# M993.net
KiCad netlist of a schematic drawn in EAGLE
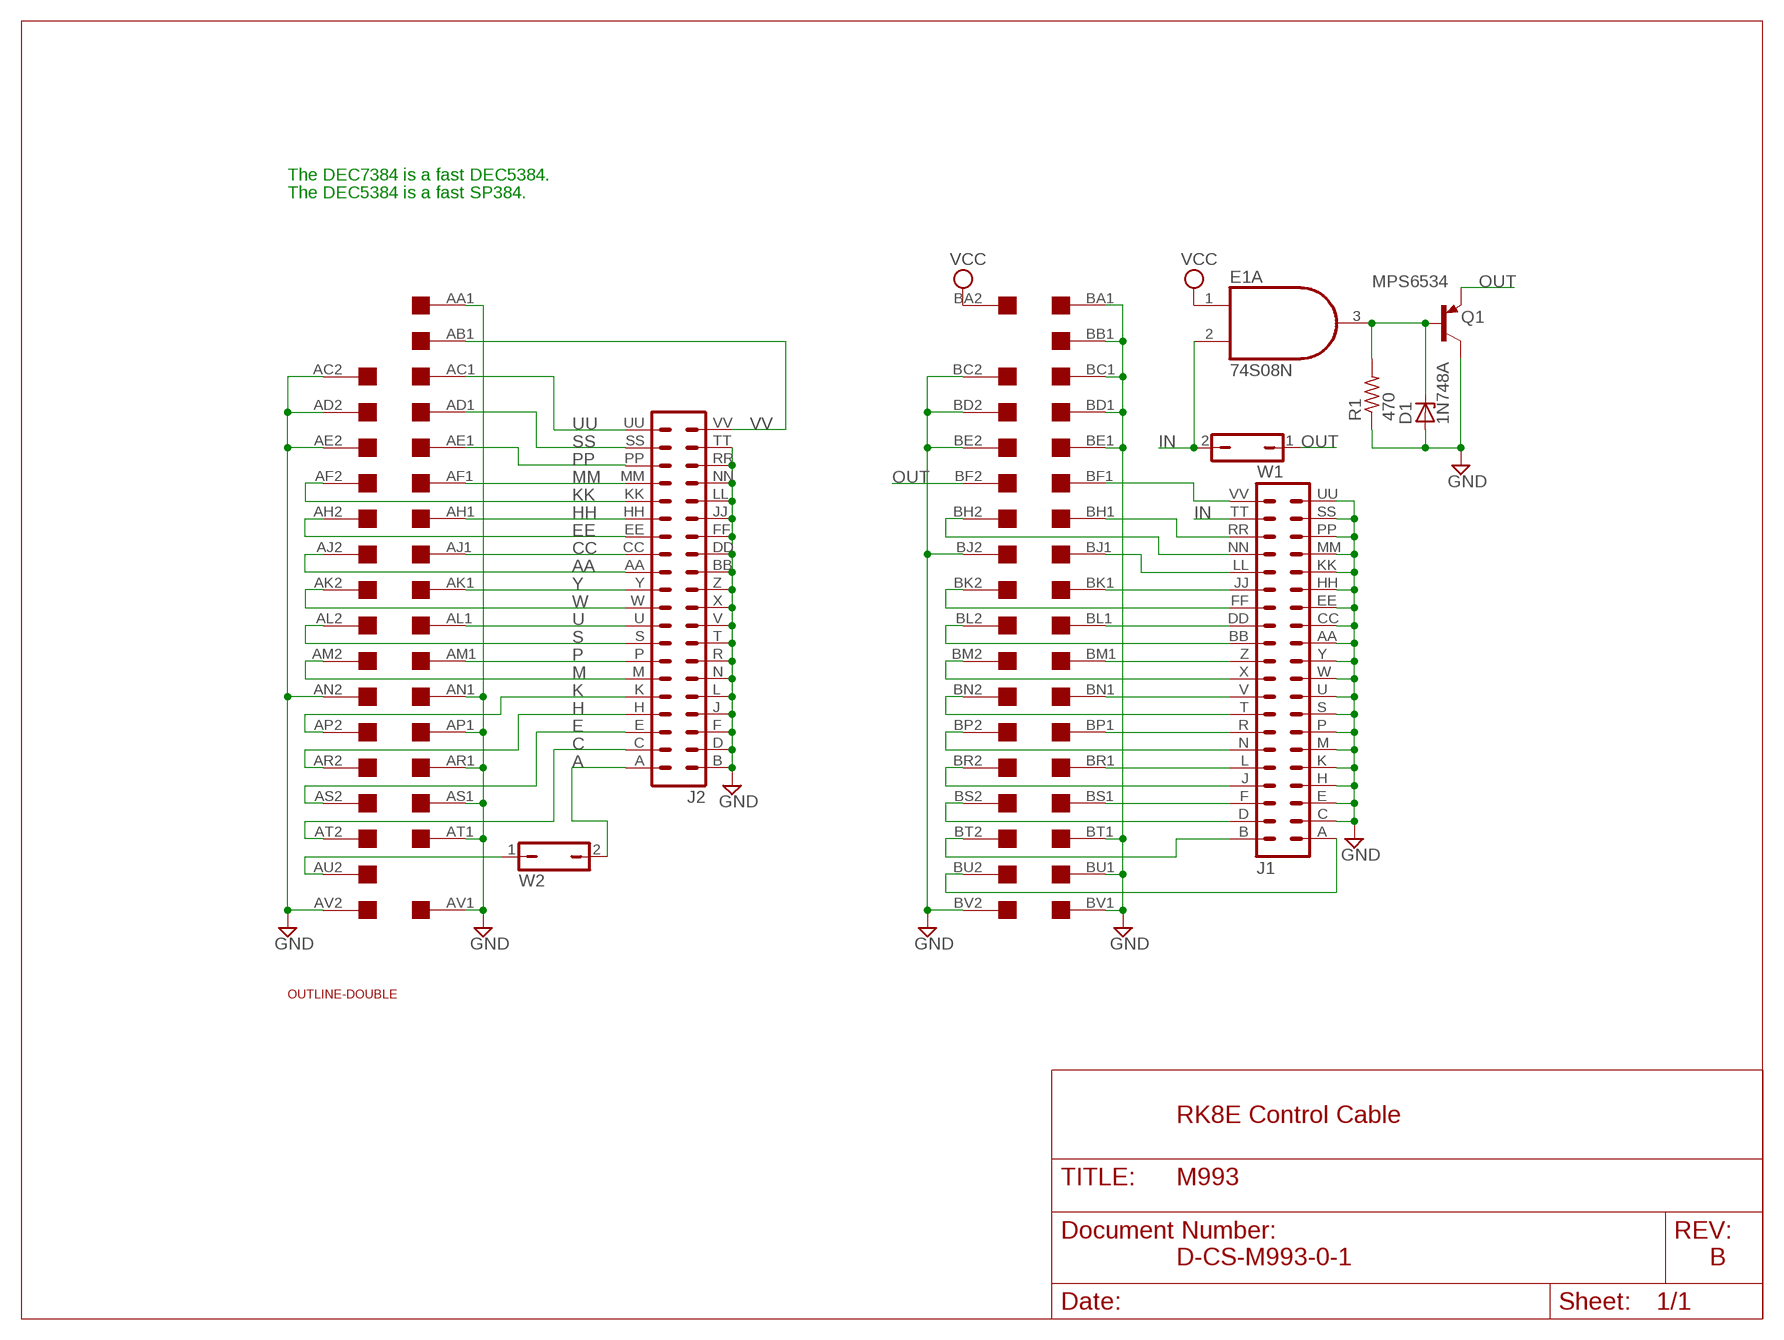
[diagram p0: schematic, sheet 1]

(export (version "E")
  (design (tool "Eeschema 10.0.6"))
  (components
    (comp (ref "D1")
      (value "1N748A")
      (footprint "eagle-import:ZDIO-10")
      (libsource (lib "eagle-import") (part "ZENER-DIODEZD-10"))
    )
    (comp (ref "E1")
      (value "74S08N")
      (footprint "eagle-import:DIL14")
      (libsource (lib "eagle-import") (part "7408NS"))
    )
    (comp (ref "J1")
      (value "DEC40PINH")
      (footprint "eagle-import:DEC40PINH")
      (libsource (lib "eagle-import") (part "DEC40PINH"))
    )
    (comp (ref "J2")
      (value "DEC40PINH")
      (footprint "eagle-import:DEC40PINH")
      (libsource (lib "eagle-import") (part "DEC40PINH"))
    )
    (comp (ref "Q1")
      (value "MPS6534")
      (footprint "eagle-import:TO92")
      (libsource (lib "eagle-import") (part "-PNP-TO92"))
    )
    (comp (ref "R1")
      (value "470")
      (footprint "eagle-import:0207_10")
      (libsource (lib "eagle-import") (part "R-US_0207/10"))
    )
    (comp (ref "U$1")
      (value "OUTLINE-DOUBLE")
      (footprint "eagle-import:DOUBLE")
      (libsource (lib "eagle-import") (part "OUTLINE-DOUBLE"))
    )
    (comp (ref "U$2")
      (value "DOUBLE")
      (footprint "eagle-import:EDGE-CON4")
      (libsource (lib "eagle-import") (part "DOUBLE"))
    )
    (comp (ref "W1")
      (value "JP1Q")
      (footprint "eagle-import:JP1")
      (libsource (lib "eagle-import") (part "JP1Q"))
    )
    (comp (ref "W2")
      (value "JP1Q")
      (footprint "eagle-import:JP1")
      (libsource (lib "eagle-import") (part "JP1Q"))
    )
  )
  (nets
    (net (code "1") (name "/A") (class "Default")
      (node (ref "J2") (pin "A") (pinfunction "1_A") (pintype "bidirectional"))
      (node (ref "W2") (pin "2") (pinfunction "2_2") (pintype "passive"))
    )
    (net (code "2") (name "/AA") (class "Default")
      (node (ref "J2") (pin "AA") (pinfunction "23_AA") (pintype "bidirectional"))
      (node (ref "U$2") (pin "AJ2") (pinfunction "1_AJ2") (pintype "bidirectional"))
    )
    (net (code "3") (name "/C") (class "Default")
      (node (ref "J2") (pin "C") (pinfunction "3_C") (pintype "bidirectional"))
      (node (ref "U$2") (pin "AT2") (pinfunction "1_AT2") (pintype "bidirectional"))
    )
    (net (code "4") (name "/CC") (class "Default")
      (node (ref "J2") (pin "CC") (pinfunction "25_CC") (pintype "bidirectional"))
      (node (ref "U$2") (pin "AJ1") (pinfunction "1_AJ1") (pintype "bidirectional"))
    )
    (net (code "5") (name "/E") (class "Default")
      (node (ref "J2") (pin "E") (pinfunction "5_E") (pintype "bidirectional"))
      (node (ref "U$2") (pin "AS2") (pinfunction "1_AS2") (pintype "bidirectional"))
    )
    (net (code "6") (name "/EE") (class "Default")
      (node (ref "J2") (pin "EE") (pinfunction "27_EE") (pintype "bidirectional"))
      (node (ref "U$2") (pin "AH2") (pinfunction "1_AH2") (pintype "bidirectional"))
    )
    (net (code "7") (name "/H") (class "Default")
      (node (ref "J2") (pin "H") (pinfunction "7_H") (pintype "bidirectional"))
      (node (ref "U$2") (pin "AR2") (pinfunction "1_AR2") (pintype "bidirectional"))
    )
    (net (code "8") (name "/HH") (class "Default")
      (node (ref "J2") (pin "HH") (pinfunction "29_HH") (pintype "bidirectional"))
      (node (ref "U$2") (pin "AH1") (pinfunction "1_AH1") (pintype "bidirectional"))
    )
    (net (code "9") (name "/IN") (class "Default")
      (node (ref "E1") (pin "2") (pinfunction "I1_2") (pintype "input"))
      (node (ref "J1") (pin "TT") (pinfunction "38_TT") (pintype "bidirectional"))
      (node (ref "W1") (pin "2") (pinfunction "2_2") (pintype "passive"))
    )
    (net (code "10") (name "/K") (class "Default")
      (node (ref "J2") (pin "K") (pinfunction "9_K") (pintype "bidirectional"))
      (node (ref "U$2") (pin "AP2") (pinfunction "1_AP2") (pintype "bidirectional"))
    )
    (net (code "11") (name "/KK") (class "Default")
      (node (ref "J2") (pin "KK") (pinfunction "31_KK") (pintype "bidirectional"))
      (node (ref "U$2") (pin "AF2") (pinfunction "1_AF2") (pintype "bidirectional"))
    )
    (net (code "12") (name "/M") (class "Default")
      (node (ref "J2") (pin "M") (pinfunction "11_M") (pintype "bidirectional"))
      (node (ref "U$2") (pin "AM2") (pinfunction "1_AM2") (pintype "bidirectional"))
    )
    (net (code "13") (name "/MM") (class "Default")
      (node (ref "J2") (pin "MM") (pinfunction "33_MM") (pintype "bidirectional"))
      (node (ref "U$2") (pin "AF1") (pinfunction "1_AF1") (pintype "bidirectional"))
    )
    (net (code "14") (name "/OUT") (class "Default")
      (node (ref "Q1") (pin "1") (pinfunction "E_1") (pintype "passive"))
      (node (ref "U$2") (pin "BF2") (pinfunction "1_BF2") (pintype "bidirectional"))
      (node (ref "W1") (pin "1") (pinfunction "1_1") (pintype "passive"))
    )
    (net (code "15") (name "/P") (class "Default")
      (node (ref "J2") (pin "P") (pinfunction "13_P") (pintype "bidirectional"))
      (node (ref "U$2") (pin "AM1") (pinfunction "1_AM1") (pintype "bidirectional"))
    )
    (net (code "16") (name "/PP") (class "Default")
      (node (ref "J2") (pin "PP") (pinfunction "35_PP") (pintype "bidirectional"))
      (node (ref "U$2") (pin "AE1") (pinfunction "1_AE1") (pintype "bidirectional"))
    )
    (net (code "17") (name "/S") (class "Default")
      (node (ref "J2") (pin "S") (pinfunction "15_S") (pintype "bidirectional"))
      (node (ref "U$2") (pin "AL2") (pinfunction "1_AL2") (pintype "bidirectional"))
    )
    (net (code "18") (name "/SS") (class "Default")
      (node (ref "J2") (pin "SS") (pinfunction "37_SS") (pintype "bidirectional"))
      (node (ref "U$2") (pin "AD1") (pinfunction "1_AD1") (pintype "bidirectional"))
    )
    (net (code "19") (name "/U") (class "Default")
      (node (ref "J2") (pin "U") (pinfunction "17_U") (pintype "bidirectional"))
      (node (ref "U$2") (pin "AL1") (pinfunction "1_AL1") (pintype "bidirectional"))
    )
    (net (code "20") (name "/UU") (class "Default")
      (node (ref "J2") (pin "UU") (pinfunction "39_UU") (pintype "bidirectional"))
      (node (ref "U$2") (pin "AC1") (pinfunction "1_AC1") (pintype "bidirectional"))
    )
    (net (code "21") (name "/VV") (class "Default")
      (node (ref "J2") (pin "VV") (pinfunction "40_VV") (pintype "bidirectional"))
      (node (ref "U$2") (pin "AB1") (pinfunction "1_AB1") (pintype "bidirectional"))
    )
    (net (code "22") (name "/W") (class "Default")
      (node (ref "J2") (pin "W") (pinfunction "19_W") (pintype "bidirectional"))
      (node (ref "U$2") (pin "AK2") (pinfunction "1_AK2") (pintype "bidirectional"))
    )
    (net (code "23") (name "/Y") (class "Default")
      (node (ref "J2") (pin "Y") (pinfunction "21_Y") (pintype "bidirectional"))
      (node (ref "U$2") (pin "AK1") (pinfunction "1_AK1") (pintype "bidirectional"))
    )
    (net (code "24") (name "GND") (class "Default")
      (node (ref "D1") (pin "A") (pinfunction "A_A") (pintype "passive"))
      (node (ref "J1") (pin "AA") (pinfunction "23_AA") (pintype "bidirectional"))
      (node (ref "J1") (pin "C") (pinfunction "3_C") (pintype "bidirectional"))
      (node (ref "J1") (pin "CC") (pinfunction "25_CC") (pintype "bidirectional"))
      (node (ref "J1") (pin "E") (pinfunction "5_E") (pintype "bidirectional"))
      (node (ref "J1") (pin "EE") (pinfunction "27_EE") (pintype "bidirectional"))
      (node (ref "J1") (pin "H") (pinfunction "7_H") (pintype "bidirectional"))
      (node (ref "J1") (pin "HH") (pinfunction "29_HH") (pintype "bidirectional"))
      (node (ref "J1") (pin "K") (pinfunction "9_K") (pintype "bidirectional"))
      (node (ref "J1") (pin "KK") (pinfunction "31_KK") (pintype "bidirectional"))
      (node (ref "J1") (pin "M") (pinfunction "11_M") (pintype "bidirectional"))
      (node (ref "J1") (pin "MM") (pinfunction "33_MM") (pintype "bidirectional"))
      (node (ref "J1") (pin "P") (pinfunction "13_P") (pintype "bidirectional"))
      (node (ref "J1") (pin "PP") (pinfunction "35_PP") (pintype "bidirectional"))
      (node (ref "J1") (pin "S") (pinfunction "15_S") (pintype "bidirectional"))
      (node (ref "J1") (pin "SS") (pinfunction "37_SS") (pintype "bidirectional"))
      (node (ref "J1") (pin "U") (pinfunction "17_U") (pintype "bidirectional"))
      (node (ref "J1") (pin "UU") (pinfunction "39_UU") (pintype "bidirectional"))
      (node (ref "J1") (pin "W") (pinfunction "19_W") (pintype "bidirectional"))
      (node (ref "J1") (pin "Y") (pinfunction "21_Y") (pintype "bidirectional"))
      (node (ref "J2") (pin "B") (pinfunction "2_B") (pintype "bidirectional"))
      (node (ref "J2") (pin "BB") (pinfunction "24_BB") (pintype "bidirectional"))
      (node (ref "J2") (pin "D") (pinfunction "4_D") (pintype "bidirectional"))
      (node (ref "J2") (pin "DD") (pinfunction "26_DD") (pintype "bidirectional"))
      (node (ref "J2") (pin "F") (pinfunction "6_F") (pintype "bidirectional"))
      (node (ref "J2") (pin "FF") (pinfunction "28_FF") (pintype "bidirectional"))
      (node (ref "J2") (pin "J") (pinfunction "8_J") (pintype "bidirectional"))
      (node (ref "J2") (pin "JJ") (pinfunction "30_JJ") (pintype "bidirectional"))
      (node (ref "J2") (pin "L") (pinfunction "10_L") (pintype "bidirectional"))
      (node (ref "J2") (pin "LL") (pinfunction "32_LL") (pintype "bidirectional"))
      (node (ref "J2") (pin "N") (pinfunction "12_N") (pintype "bidirectional"))
      (node (ref "J2") (pin "NN") (pinfunction "34_NN") (pintype "bidirectional"))
      (node (ref "J2") (pin "R") (pinfunction "14_R") (pintype "bidirectional"))
      (node (ref "J2") (pin "RR") (pinfunction "36_RR") (pintype "bidirectional"))
      (node (ref "J2") (pin "T") (pinfunction "16_T") (pintype "bidirectional"))
      (node (ref "J2") (pin "TT") (pinfunction "38_TT") (pintype "bidirectional"))
      (node (ref "J2") (pin "V") (pinfunction "18_V") (pintype "bidirectional"))
      (node (ref "J2") (pin "X") (pinfunction "20_X") (pintype "bidirectional"))
      (node (ref "J2") (pin "Z") (pinfunction "22_Z") (pintype "bidirectional"))
      (node (ref "Q1") (pin "3") (pinfunction "C_3") (pintype "passive"))
      (node (ref "R1") (pin "1") (pinfunction "1_1") (pintype "passive"))
      (node (ref "U$2") (pin "AA1") (pinfunction "1_AA1") (pintype "bidirectional"))
      (node (ref "U$2") (pin "AC2") (pinfunction "1_AC2") (pintype "bidirectional"))
      (node (ref "U$2") (pin "AD2") (pinfunction "1_AD2") (pintype "bidirectional"))
      (node (ref "U$2") (pin "AE2") (pinfunction "1_AE2") (pintype "bidirectional"))
      (node (ref "U$2") (pin "AN1") (pinfunction "1_AN1") (pintype "bidirectional"))
      (node (ref "U$2") (pin "AN2") (pinfunction "1_AN2") (pintype "bidirectional"))
      (node (ref "U$2") (pin "AP1") (pinfunction "1_AP1") (pintype "bidirectional"))
      (node (ref "U$2") (pin "AR1") (pinfunction "1_AR1") (pintype "bidirectional"))
      (node (ref "U$2") (pin "AS1") (pinfunction "1_AS1") (pintype "bidirectional"))
      (node (ref "U$2") (pin "AT1") (pinfunction "1_AT1") (pintype "bidirectional"))
      (node (ref "U$2") (pin "AV1") (pinfunction "1_AV1") (pintype "bidirectional"))
      (node (ref "U$2") (pin "AV2") (pinfunction "1_AV2") (pintype "bidirectional"))
      (node (ref "U$2") (pin "BA1") (pinfunction "1_BA1") (pintype "bidirectional"))
      (node (ref "U$2") (pin "BB1") (pinfunction "1_BB1") (pintype "bidirectional"))
      (node (ref "U$2") (pin "BC1") (pinfunction "1_BC1") (pintype "bidirectional"))
      (node (ref "U$2") (pin "BC2") (pinfunction "1_BC2") (pintype "bidirectional"))
      (node (ref "U$2") (pin "BD1") (pinfunction "1_BD1") (pintype "bidirectional"))
      (node (ref "U$2") (pin "BD2") (pinfunction "1_BD2") (pintype "bidirectional"))
      (node (ref "U$2") (pin "BE1") (pinfunction "1_BE1") (pintype "bidirectional"))
      (node (ref "U$2") (pin "BE2") (pinfunction "1_BE2") (pintype "bidirectional"))
      (node (ref "U$2") (pin "BJ2") (pinfunction "1_BJ2") (pintype "bidirectional"))
      (node (ref "U$2") (pin "BT1") (pinfunction "1_BT1") (pintype "bidirectional"))
      (node (ref "U$2") (pin "BU1") (pinfunction "1_BU1") (pintype "bidirectional"))
      (node (ref "U$2") (pin "BV1") (pinfunction "1_BV1") (pintype "bidirectional"))
      (node (ref "U$2") (pin "BV2") (pinfunction "1_BV2") (pintype "bidirectional"))
    )
    (net (code "25") (name "Net-(E1A-O)") (class "Default")
      (node (ref "D1") (pin "C") (pinfunction "C_C") (pintype "passive"))
      (node (ref "E1") (pin "3") (pinfunction "O_3") (pintype "output"))
      (node (ref "Q1") (pin "2") (pinfunction "B_2") (pintype "passive"))
      (node (ref "R1") (pin "2") (pinfunction "2_2") (pintype "passive"))
    )
    (net (code "26") (name "Net-(J1-1)") (class "Default")
      (node (ref "J1") (pin "A") (pinfunction "1_A") (pintype "bidirectional"))
      (node (ref "U$2") (pin "BU2") (pinfunction "1_BU2") (pintype "bidirectional"))
    )
    (net (code "27") (name "Net-(J1-2)") (class "Default")
      (node (ref "J1") (pin "B") (pinfunction "2_B") (pintype "bidirectional"))
      (node (ref "U$2") (pin "BT2") (pinfunction "1_BT2") (pintype "bidirectional"))
    )
    (net (code "28") (name "Net-(J1-4)") (class "Default")
      (node (ref "J1") (pin "D") (pinfunction "4_D") (pintype "bidirectional"))
      (node (ref "U$2") (pin "BS2") (pinfunction "1_BS2") (pintype "bidirectional"))
    )
    (net (code "29") (name "Net-(J1-6)") (class "Default")
      (node (ref "J1") (pin "F") (pinfunction "6_F") (pintype "bidirectional"))
      (node (ref "U$2") (pin "BS1") (pinfunction "1_BS1") (pintype "bidirectional"))
    )
    (net (code "30") (name "Net-(J1-8)") (class "Default")
      (node (ref "J1") (pin "J") (pinfunction "8_J") (pintype "bidirectional"))
      (node (ref "U$2") (pin "BR2") (pinfunction "1_BR2") (pintype "bidirectional"))
    )
    (net (code "31") (name "Net-(J1-10)") (class "Default")
      (node (ref "J1") (pin "L") (pinfunction "10_L") (pintype "bidirectional"))
      (node (ref "U$2") (pin "BR1") (pinfunction "1_BR1") (pintype "bidirectional"))
    )
    (net (code "32") (name "Net-(J1-12)") (class "Default")
      (node (ref "J1") (pin "N") (pinfunction "12_N") (pintype "bidirectional"))
      (node (ref "U$2") (pin "BP2") (pinfunction "1_BP2") (pintype "bidirectional"))
    )
    (net (code "33") (name "Net-(J1-14)") (class "Default")
      (node (ref "J1") (pin "R") (pinfunction "14_R") (pintype "bidirectional"))
      (node (ref "U$2") (pin "BP1") (pinfunction "1_BP1") (pintype "bidirectional"))
    )
    (net (code "34") (name "Net-(J1-16)") (class "Default")
      (node (ref "J1") (pin "T") (pinfunction "16_T") (pintype "bidirectional"))
      (node (ref "U$2") (pin "BN2") (pinfunction "1_BN2") (pintype "bidirectional"))
    )
    (net (code "35") (name "Net-(J1-18)") (class "Default")
      (node (ref "J1") (pin "V") (pinfunction "18_V") (pintype "bidirectional"))
      (node (ref "U$2") (pin "BN1") (pinfunction "1_BN1") (pintype "bidirectional"))
    )
    (net (code "36") (name "Net-(J1-20)") (class "Default")
      (node (ref "J1") (pin "X") (pinfunction "20_X") (pintype "bidirectional"))
      (node (ref "U$2") (pin "BM2") (pinfunction "1_BM2") (pintype "bidirectional"))
    )
    (net (code "37") (name "Net-(J1-22)") (class "Default")
      (node (ref "J1") (pin "Z") (pinfunction "22_Z") (pintype "bidirectional"))
      (node (ref "U$2") (pin "BM1") (pinfunction "1_BM1") (pintype "bidirectional"))
    )
    (net (code "38") (name "Net-(J1-24)") (class "Default")
      (node (ref "J1") (pin "BB") (pinfunction "24_BB") (pintype "bidirectional"))
      (node (ref "U$2") (pin "BL2") (pinfunction "1_BL2") (pintype "bidirectional"))
    )
    (net (code "39") (name "Net-(J1-26)") (class "Default")
      (node (ref "J1") (pin "DD") (pinfunction "26_DD") (pintype "bidirectional"))
      (node (ref "U$2") (pin "BL1") (pinfunction "1_BL1") (pintype "bidirectional"))
    )
    (net (code "40") (name "Net-(J1-28)") (class "Default")
      (node (ref "J1") (pin "FF") (pinfunction "28_FF") (pintype "bidirectional"))
      (node (ref "U$2") (pin "BK2") (pinfunction "1_BK2") (pintype "bidirectional"))
    )
    (net (code "41") (name "Net-(J1-30)") (class "Default")
      (node (ref "J1") (pin "JJ") (pinfunction "30_JJ") (pintype "bidirectional"))
      (node (ref "U$2") (pin "BK1") (pinfunction "1_BK1") (pintype "bidirectional"))
    )
    (net (code "42") (name "Net-(J1-32)") (class "Default")
      (node (ref "J1") (pin "LL") (pinfunction "32_LL") (pintype "bidirectional"))
      (node (ref "U$2") (pin "BJ1") (pinfunction "1_BJ1") (pintype "bidirectional"))
    )
    (net (code "43") (name "Net-(J1-34)") (class "Default")
      (node (ref "J1") (pin "NN") (pinfunction "34_NN") (pintype "bidirectional"))
      (node (ref "U$2") (pin "BH2") (pinfunction "1_BH2") (pintype "bidirectional"))
    )
    (net (code "44") (name "Net-(J1-36)") (class "Default")
      (node (ref "J1") (pin "RR") (pinfunction "36_RR") (pintype "bidirectional"))
      (node (ref "U$2") (pin "BH1") (pinfunction "1_BH1") (pintype "bidirectional"))
    )
    (net (code "45") (name "Net-(J1-40)") (class "Default")
      (node (ref "J1") (pin "VV") (pinfunction "40_VV") (pintype "bidirectional"))
      (node (ref "U$2") (pin "BF1") (pinfunction "1_BF1") (pintype "bidirectional"))
    )
    (net (code "46") (name "Net-(U$2AH-1)") (class "Default")
      (node (ref "U$2") (pin "AU2") (pinfunction "1_AU2") (pintype "bidirectional"))
      (node (ref "W2") (pin "1") (pinfunction "1_1") (pintype "passive"))
    )
    (net (code "47") (name "VCC") (class "Default")
      (node (ref "E1") (pin "1") (pinfunction "I0_1") (pintype "input"))
      (node (ref "U$2") (pin "BA2") (pinfunction "1_BA2") (pintype "bidirectional"))
    )
  )
)
